# interconnect.net
KiCad netlist of a schematic drawn in Altium Designer
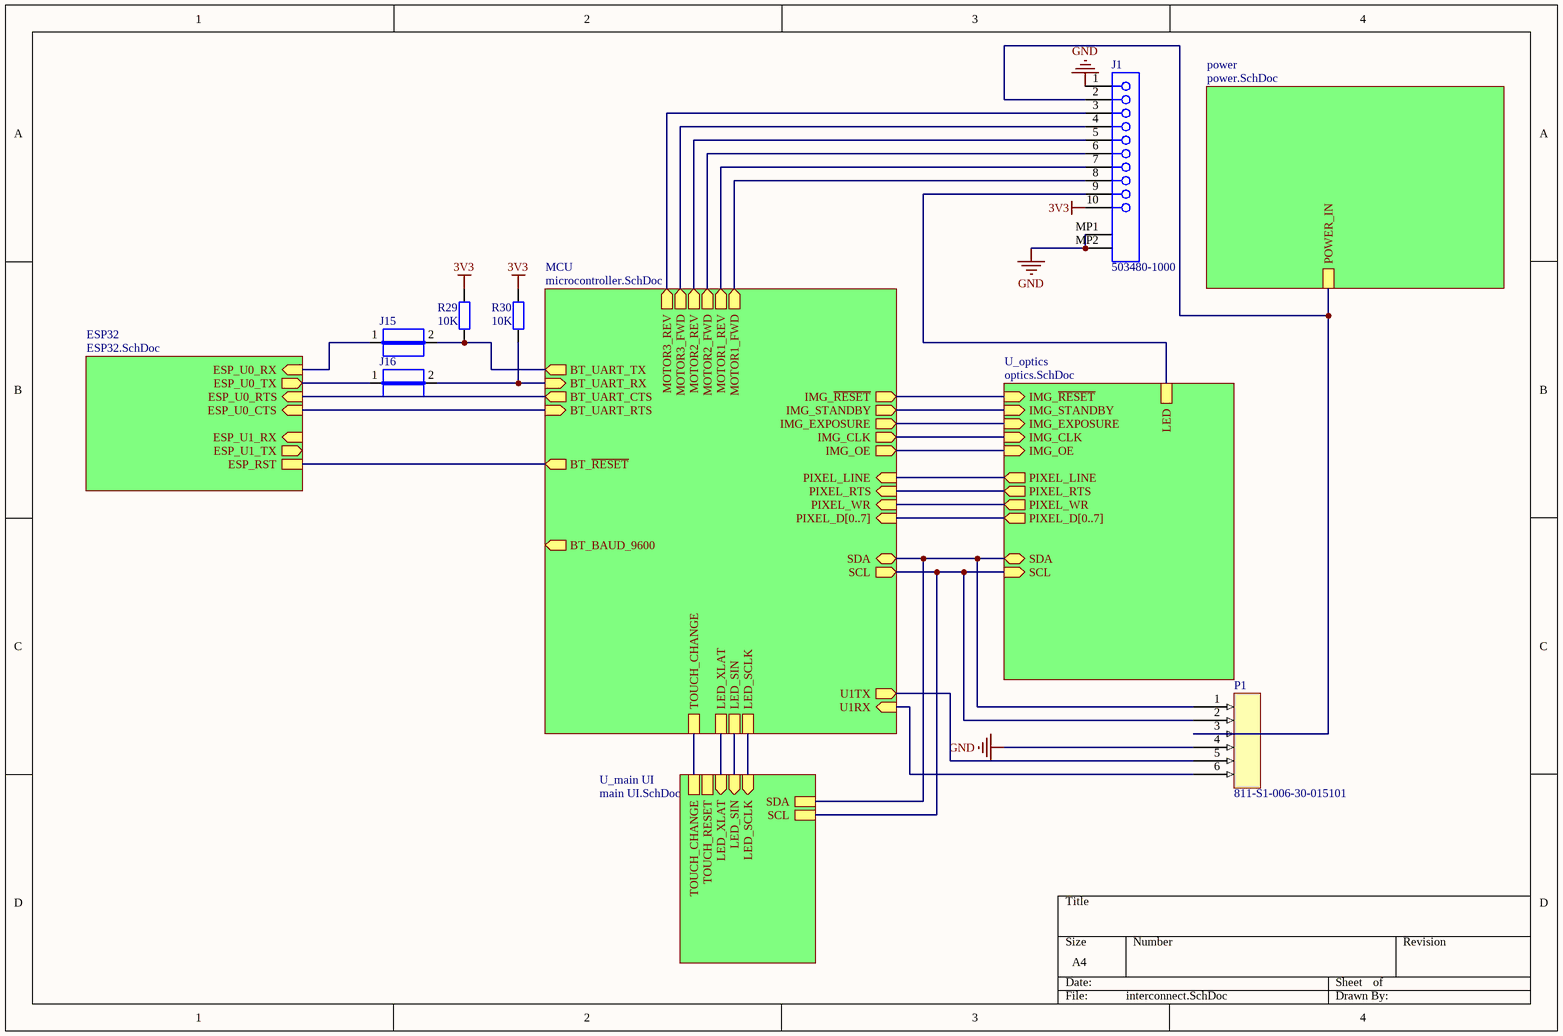
[diagram p0: interconnect.SchDoc]

(export (version "E")
  (design (tool "Eeschema 10.0.6"))
  (components
    (comp (ref "J1")
      (value "503480-1000")
      (footprint "MOLX-503480-1000")
      (fields (field (name "MANUFACTURER") "Molex"))
      (libsource (lib "Altium Content Vault") (part "MOLX-503480-1000"))
    )
    (comp (ref "J15") (value "JUMPER") (footprint "JUMPER") (libsource (lib "EPFL") (part "JUMPER")))
    (comp (ref "J16") (value "JUMPER") (footprint "JUMPER") (libsource (lib "EPFL") (part "JUMPER")))
    (comp (ref "P1")
      (value "811-S1-006-30-015101")
      (footprint "New footprint 1")
      (description "Conn Spring Piston 6POS SMD")
      (libsource (lib "EPFL") (part "New symbol 1"))
    )
    (comp (ref "R29")
      (value "10K")
      (footprint "TwoTerminal:1608[0603]_M")
      (description "Generic Resistor")
      (libsource (lib "Passive") (part "Resistor"))
    )
    (comp (ref "R30")
      (value "10K")
      (footprint "TwoTerminal:1608[0603]_M")
      (description "Generic Resistor")
      (libsource (lib "Passive") (part "Resistor"))
    )
  )
  (nets
    (net (code "4") (name "/BT_UART_RX") (class "Default")
      (node (ref "J16") (pin "2") (pinfunction "2_2") (pintype "passive"))
      (node (ref "R30") (pin "1") (pinfunction "1_1") (pintype "passive"))
    )
    (net (code "5") (name "/BT_UART_TX") (class "Default")
      (node (ref "J15") (pin "2") (pinfunction "2_2") (pintype "passive"))
      (node (ref "R29") (pin "1") (pinfunction "1_1") (pintype "passive"))
    )
    (net (code "7") (name "/ESP_U0_RX") (class "Default")
      (node (ref "J15") (pin "1") (pinfunction "1_1") (pintype "passive"))
    )
    (net (code "8") (name "/ESP_U0_TX") (class "Default")
      (node (ref "J16") (pin "1") (pinfunction "1_1") (pintype "passive"))
    )
    (net (code "16") (name "/LED") (class "Default")
      (node (ref "J1") (pin "9") (pinfunction "9_9") (pintype "passive"))
    )
    (net (code "20") (name "/MOTOR1_FWD") (class "Default")
      (node (ref "J1") (pin "8") (pinfunction "8_8") (pintype "passive"))
    )
    (net (code "21") (name "/MOTOR1_REV") (class "Default")
      (node (ref "J1") (pin "7") (pinfunction "7_7") (pintype "passive"))
    )
    (net (code "22") (name "/MOTOR2_FWD") (class "Default")
      (node (ref "J1") (pin "6") (pinfunction "6_6") (pintype "passive"))
    )
    (net (code "23") (name "/MOTOR2_REV") (class "Default")
      (node (ref "J1") (pin "5") (pinfunction "5_5") (pintype "passive"))
    )
    (net (code "24") (name "/MOTOR3_FWD") (class "Default")
      (node (ref "J1") (pin "4") (pinfunction "4_4") (pintype "passive"))
    )
    (net (code "25") (name "/MOTOR3_REV") (class "Default")
      (node (ref "J1") (pin "3") (pinfunction "3_3") (pintype "passive"))
    )
    (net (code "30") (name "/POWER_IN") (class "Default")
      (node (ref "J1") (pin "2") (pinfunction "2_2") (pintype "passive"))
      (node (ref "P1") (pin "3") (pintype "input"))
    )
    (net (code "31") (name "/SCL") (class "Default") (node (ref "P1") (pin "2") (pintype "input")))
    (net (code "32") (name "/SDA") (class "Default") (node (ref "P1") (pin "1") (pintype "input")))
    (net (code "35") (name "/U1RX") (class "Default") (node (ref "P1") (pin "6") (pintype "input")))
    (net (code "36") (name "/U1TX") (class "Default") (node (ref "P1") (pin "5") (pintype "input")))
    (net (code "37") (name "3V3") (class "Default")
      (node (ref "J1") (pin "10") (pinfunction "10_10") (pintype "passive"))
      (node (ref "R29") (pin "2") (pinfunction "2_2") (pintype "passive"))
      (node (ref "R30") (pin "2") (pinfunction "2_2") (pintype "passive"))
    )
    (net (code "38") (name "GND") (class "Default")
      (node (ref "J1") (pin "1") (pinfunction "1_1") (pintype "passive"))
      (node (ref "J1") (pin "MP1") (pinfunction "MP1_MP1") (pintype "passive"))
      (node (ref "J1") (pin "MP2") (pinfunction "MP2_MP2") (pintype "passive"))
      (node (ref "P1") (pin "4") (pintype "input"))
    )
  )
)
